# power_sheet.net
KiCad netlist of a schematic drawn in Altium Designer
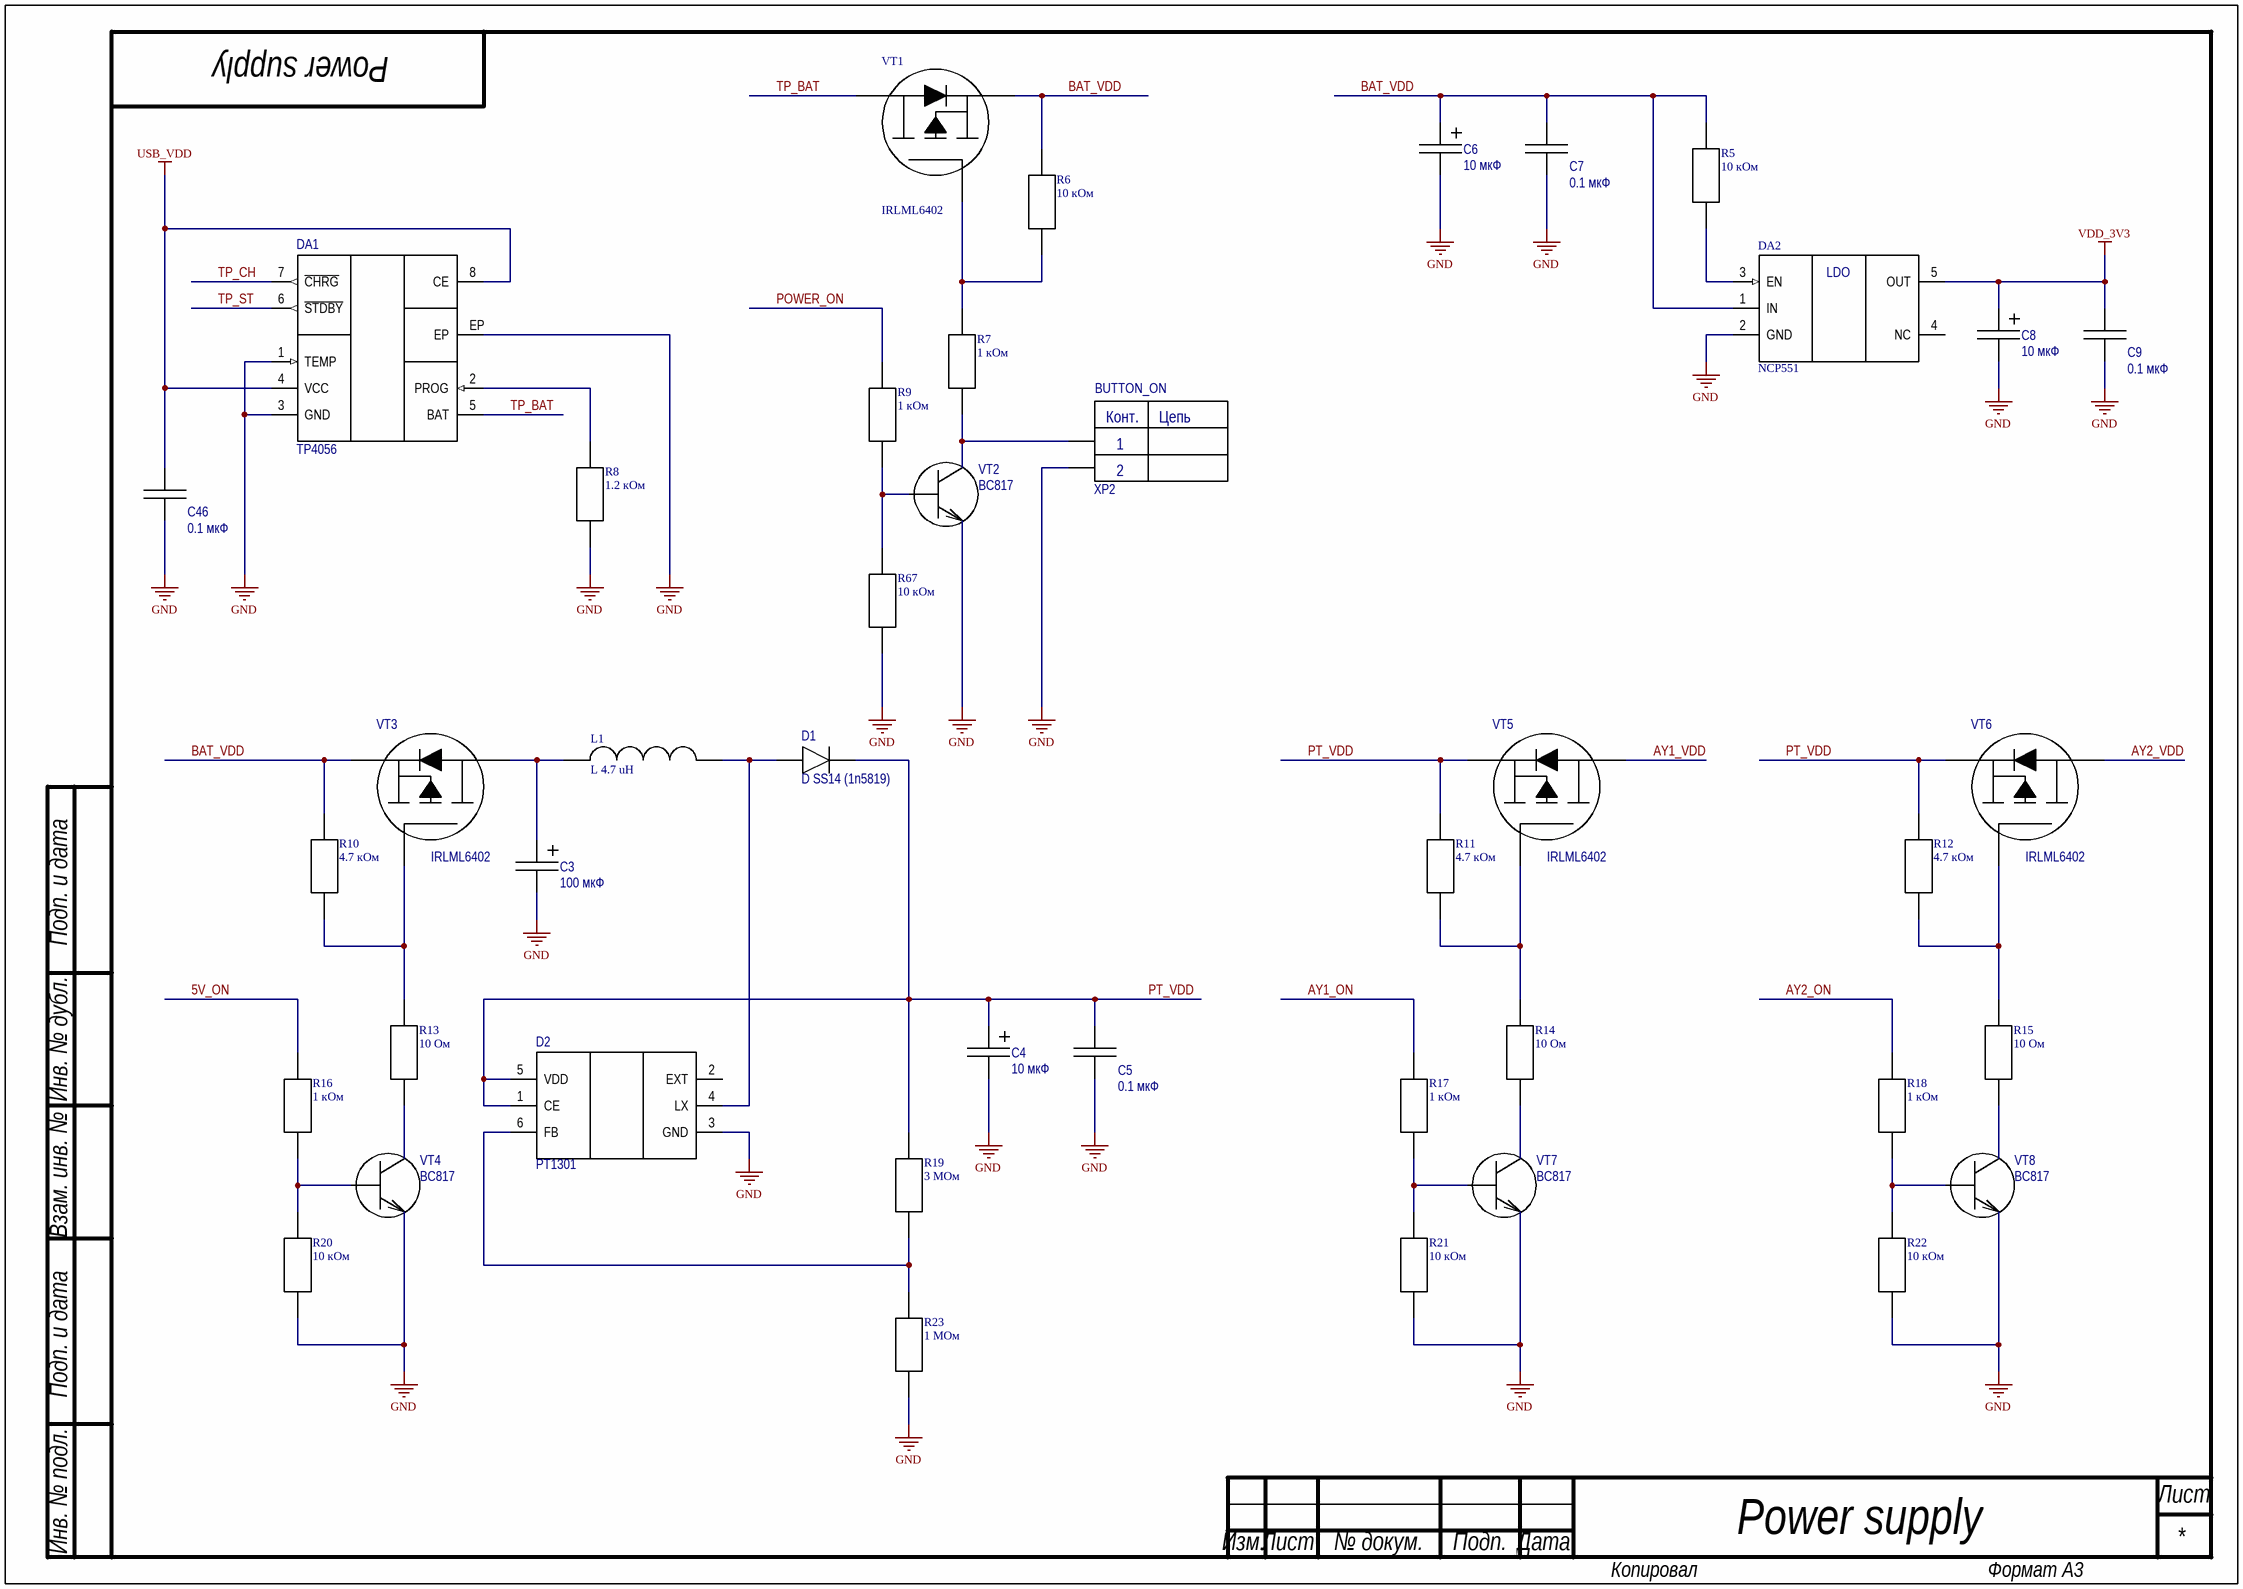
[diagram p0: power_sheet.SchDoc]

(export (version "E")
  (design (tool "Eeschema 10.0.6"))
  (components
    (comp (ref "C3")
      (value "100 мкФ")
      (footprint "C TAN_D")
      (description "SMD Tantalium Capacitor D")
      (fields
        (field (name "TOLERANCE") "/Укажите допуск в процентах/")
        (field (name "MANUFACTURER") "/Укажите компанию-производителя/")
      )
      (libsource (lib "my_lib") (part "CAP TAN_D"))
    )
    (comp (ref "C4")
      (value "10 мкФ")
      (footprint "C TAN_C")
      (description "SMD Tantalium Capacitor C")
      (fields
        (field (name "TOLERANCE") "/Укажите допуск в процентах/")
        (field (name "MANUFACTURER") "/Укажите компанию-производителя/")
      )
      (libsource (lib "my_lib") (part "CAP TAN_C"))
    )
    (comp (ref "C5")
      (value "0.1 мкФ")
      (footprint "C 1206")
      (description "SMD Capacitor 1206")
      (fields
        (field (name "TOLERANCE") "/Укажите допуск в процентах/")
        (field (name "MANUFACTURER") "/Укажите компанию-производителя/")
      )
      (libsource (lib "my_lib") (part "CAP 1206"))
    )
    (comp (ref "C6")
      (value "10 мкФ")
      (footprint "C TAN_C")
      (description "SMD Tantalium Capacitor C")
      (fields
        (field (name "TOLERANCE") "/Укажите допуск в процентах/")
        (field (name "MANUFACTURER") "/Укажите компанию-производителя/")
      )
      (libsource (lib "my_lib") (part "CAP TAN_C"))
    )
    (comp (ref "C7")
      (value "0.1 мкФ")
      (footprint "C 1206")
      (description "SMD Capacitor 1206")
      (fields
        (field (name "TOLERANCE") "/Укажите допуск в процентах/")
        (field (name "MANUFACTURER") "/Укажите компанию-производителя/")
      )
      (libsource (lib "my_lib") (part "CAP 1206"))
    )
    (comp (ref "C8")
      (value "10 мкФ")
      (footprint "C TAN_C")
      (description "SMD Tantalium Capacitor C")
      (fields
        (field (name "TOLERANCE") "/Укажите допуск в процентах/")
        (field (name "MANUFACTURER") "/Укажите компанию-производителя/")
      )
      (libsource (lib "my_lib") (part "CAP TAN_C"))
    )
    (comp (ref "C9")
      (value "0.1 мкФ")
      (footprint "C 1206")
      (description "SMD Capacitor 1206")
      (fields
        (field (name "TOLERANCE") "/Укажите допуск в процентах/")
        (field (name "MANUFACTURER") "/Укажите компанию-производителя/")
      )
      (libsource (lib "my_lib") (part "CAP 1206"))
    )
    (comp (ref "C46")
      (value "0.1 мкФ")
      (footprint "C 1206")
      (description "SMD Capacitor 1206")
      (fields
        (field (name "TOLERANCE") "/Укажите допуск в процентах/")
        (field (name "MANUFACTURER") "/Укажите компанию-производителя/")
      )
      (libsource (lib "my_lib") (part "CAP 1206"))
    )
    (comp (ref "D1")
      (value "D SS14 (1n5819)")
      (footprint "SMA/DO-214AC")
      (libsource (lib "my_lib") (part "D SS14 (1n5819)"))
    )
    (comp (ref "D2")
      (value "PT1301")
      (footprint "SOT-23-6")
      (description "DC-DC step-up (повышающий) PT1301 в корпусе SOT23-6.")
      (libsource (lib "my_lib") (part "PT1301"))
    )
    (comp (ref "DA1") (value "TP4056") (footprint "HSOP-8") (libsource (lib "my_lib") (part "TP4056")))
    (comp (ref "DA2") (value "NCP551") (footprint "TSOP-5") (libsource (lib "my_lib") (part "NCP551")))
    (comp (ref "L1")
      (value "L 4.7 uH")
      (footprint "CD43")
      (description "Катушка индуктивности 4.7 мкГн корпус CD43 (индуктивность 4.7 uH).")
      (libsource (lib "my_lib") (part "L 4.7 uH"))
    )
    (comp (ref "R5") (value "10 кОм") (footprint "RES 0805") (libsource (lib "my_lib") (part "RES 0805")))
    (comp (ref "R6") (value "10 кОм") (footprint "RES 0805") (libsource (lib "my_lib") (part "RES 0805")))
    (comp (ref "R7") (value "1 кОм") (footprint "RES 0805") (libsource (lib "my_lib") (part "RES 0805")))
    (comp (ref "R8") (value "1.2 кОм") (footprint "RES 0805") (libsource (lib "my_lib") (part "RES 0805")))
    (comp (ref "R9") (value "1 кОм") (footprint "RES 0805") (libsource (lib "my_lib") (part "RES 0805")))
    (comp (ref "R10") (value "4.7 кОм") (footprint "RES 0805") (libsource (lib "my_lib") (part "RES 0805")))
    (comp (ref "R11") (value "4.7 кОм") (footprint "RES 0805") (libsource (lib "my_lib") (part "RES 0805")))
    (comp (ref "R12") (value "4.7 кОм") (footprint "RES 0805") (libsource (lib "my_lib") (part "RES 0805")))
    (comp (ref "R13") (value "10 Ом") (footprint "RES 0805") (libsource (lib "my_lib") (part "RES 0805")))
    (comp (ref "R14") (value "10 Ом") (footprint "RES 0805") (libsource (lib "my_lib") (part "RES 0805")))
    (comp (ref "R15") (value "10 Ом") (footprint "RES 0805") (libsource (lib "my_lib") (part "RES 0805")))
    (comp (ref "R16") (value "1 кОм") (footprint "RES 0805") (libsource (lib "my_lib") (part "RES 0805")))
    (comp (ref "R17") (value "1 кОм") (footprint "RES 0805") (libsource (lib "my_lib") (part "RES 0805")))
    (comp (ref "R18") (value "1 кОм") (footprint "RES 0805") (libsource (lib "my_lib") (part "RES 0805")))
    (comp (ref "R19") (value "3 МОм") (footprint "RES 0805") (libsource (lib "my_lib") (part "RES 0805")))
    (comp (ref "R20") (value "10 кОм") (footprint "RES 0805") (libsource (lib "my_lib") (part "RES 0805")))
    (comp (ref "R21") (value "10 кОм") (footprint "RES 0805") (libsource (lib "my_lib") (part "RES 0805")))
    (comp (ref "R22") (value "10 кОм") (footprint "RES 0805") (libsource (lib "my_lib") (part "RES 0805")))
    (comp (ref "R23") (value "1 МОм") (footprint "RES 0805") (libsource (lib "my_lib") (part "RES 0805")))
    (comp (ref "R67") (value "10 кОм") (footprint "RES 0805") (libsource (lib "my_lib") (part "RES 0805")))
    (comp (ref "VT1") (value "IRLML6402") (footprint "SOT-23") (libsource (lib "my_lib") (part "IRLML6402")))
    (comp (ref "VT2")
      (value "BC817")
      (footprint "SOT-23")
      (description "NPN general-purpose transistor")
      (fields (field (name "MANUFACTURER") "NXP"))
      (libsource (lib "my_lib") (part "BC817"))
    )
    (comp (ref "VT3") (value "IRLML6402") (footprint "SOT-23") (libsource (lib "my_lib") (part "IRLML6402")))
    (comp (ref "VT4")
      (value "BC817")
      (footprint "SOT-23")
      (description "NPN general-purpose transistor")
      (fields (field (name "MANUFACTURER") "NXP"))
      (libsource (lib "my_lib") (part "BC817"))
    )
    (comp (ref "VT5") (value "IRLML6402") (footprint "SOT-23") (libsource (lib "my_lib") (part "IRLML6402")))
    (comp (ref "VT6") (value "IRLML6402") (footprint "SOT-23") (libsource (lib "my_lib") (part "IRLML6402")))
    (comp (ref "VT7")
      (value "BC817")
      (footprint "SOT-23")
      (description "NPN general-purpose transistor")
      (fields (field (name "MANUFACTURER") "NXP"))
      (libsource (lib "my_lib") (part "BC817"))
    )
    (comp (ref "VT8")
      (value "BC817")
      (footprint "SOT-23")
      (description "NPN general-purpose transistor")
      (fields (field (name "MANUFACTURER") "NXP"))
      (libsource (lib "my_lib") (part "BC817"))
    )
    (comp (ref "XP2")
      (value "PLS-2")
      (footprint "PLS-2")
      (description "PLS connector")
      (fields (field (name "MANUFACTURER") "NONAME"))
      (libsource (lib "my_lib") (part "PLS-2"))
    )
  )
  (nets
    (net (code "1") (name "/5V_ON") (class "Default")
      (node (ref "R16") (pin "2") (pinfunction "2_2") (pintype "passive"))
    )
    (net (code "2") (name "/AY1_ON") (class "Default")
      (node (ref "R17") (pin "2") (pinfunction "2_2") (pintype "passive"))
    )
    (net (code "3") (name "/AY1_VDD") (class "Default")
      (node (ref "VT5") (pin "3") (pinfunction "D_3") (pintype "passive"))
    )
    (net (code "4") (name "/AY2_ON") (class "Default")
      (node (ref "R18") (pin "2") (pinfunction "2_2") (pintype "passive"))
    )
    (net (code "5") (name "/AY2_VDD") (class "Default")
      (node (ref "VT6") (pin "3") (pinfunction "D_3") (pintype "passive"))
    )
    (net (code "6") (name "/BAT_VDD") (class "Default")
      (node (ref "C6") (pin "1") (pinfunction "1_1") (pintype "passive"))
      (node (ref "C7") (pin "1") (pinfunction "1_1") (pintype "passive"))
      (node (ref "DA2") (pin "1") (pinfunction "IN_1") (pintype "passive"))
      (node (ref "R10") (pin "2") (pinfunction "2_2") (pintype "passive"))
      (node (ref "R5") (pin "2") (pinfunction "2_2") (pintype "passive"))
      (node (ref "R6") (pin "2") (pinfunction "2_2") (pintype "passive"))
      (node (ref "VT1") (pin "2") (pinfunction "S_2") (pintype "passive"))
      (node (ref "VT3") (pin "2") (pinfunction "S_2") (pintype "passive"))
    )
    (net (code "7") (name "/POWER_ON") (class "Default")
      (node (ref "R9") (pin "2") (pinfunction "2_2") (pintype "passive"))
    )
    (net (code "8") (name "/PT_VDD") (class "Default")
      (node (ref "C4") (pin "1") (pinfunction "1_1") (pintype "passive"))
      (node (ref "C5") (pin "1") (pinfunction "1_1") (pintype "passive"))
      (node (ref "D1") (pin "C") (pinfunction "C_C") (pintype "passive"))
      (node (ref "D2") (pin "1") (pinfunction "CE_1") (pintype "passive"))
      (node (ref "D2") (pin "5") (pinfunction "VDD_5") (pintype "passive"))
      (node (ref "R11") (pin "2") (pinfunction "2_2") (pintype "passive"))
      (node (ref "R12") (pin "2") (pinfunction "2_2") (pintype "passive"))
      (node (ref "R19") (pin "2") (pinfunction "2_2") (pintype "passive"))
      (node (ref "VT5") (pin "2") (pinfunction "S_2") (pintype "passive"))
      (node (ref "VT6") (pin "2") (pinfunction "S_2") (pintype "passive"))
    )
    (net (code "9") (name "/TP_BAT") (class "Default")
      (node (ref "DA1") (pin "5") (pinfunction "BAT_5") (pintype "power_in"))
      (node (ref "VT1") (pin "3") (pinfunction "D_3") (pintype "passive"))
    )
    (net (code "10") (name "/TP_CH") (class "Default")
      (node (ref "DA1") (pin "7") (pinfunction "~{CHRG}_7") (pintype "output"))
    )
    (net (code "11") (name "/TP_ST") (class "Default")
      (node (ref "DA1") (pin "6") (pinfunction "~{STDBY}_6") (pintype "output"))
    )
    (net (code "12") (name "GND") (class "Default")
      (node (ref "C3") (pin "2") (pinfunction "2_2") (pintype "passive"))
      (node (ref "C4") (pin "2") (pinfunction "2_2") (pintype "passive"))
      (node (ref "C46") (pin "2") (pinfunction "2_2") (pintype "passive"))
      (node (ref "C5") (pin "2") (pinfunction "2_2") (pintype "passive"))
      (node (ref "C6") (pin "2") (pinfunction "2_2") (pintype "passive"))
      (node (ref "C7") (pin "2") (pinfunction "2_2") (pintype "passive"))
      (node (ref "C8") (pin "2") (pinfunction "2_2") (pintype "passive"))
      (node (ref "C9") (pin "2") (pinfunction "2_2") (pintype "passive"))
      (node (ref "D2") (pin "3") (pinfunction "GND_3") (pintype "passive"))
      (node (ref "DA1") (pin "1") (pinfunction "TEMP_1") (pintype "input"))
      (node (ref "DA1") (pin "3") (pinfunction "GND_3") (pintype "power_in"))
      (node (ref "DA1") (pin "EP") (pinfunction "EP_EP") (pintype "passive"))
      (node (ref "DA2") (pin "2") (pinfunction "GND_2") (pintype "passive"))
      (node (ref "R20") (pin "1") (pinfunction "1_1") (pintype "passive"))
      (node (ref "R21") (pin "1") (pinfunction "1_1") (pintype "passive"))
      (node (ref "R22") (pin "1") (pinfunction "1_1") (pintype "passive"))
      (node (ref "R23") (pin "1") (pinfunction "1_1") (pintype "passive"))
      (node (ref "R67") (pin "1") (pinfunction "1_1") (pintype "passive"))
      (node (ref "R8") (pin "1") (pinfunction "1_1") (pintype "passive"))
      (node (ref "VT2") (pin "2") (pinfunction "E_2") (pintype "passive"))
      (node (ref "VT4") (pin "2") (pinfunction "E_2") (pintype "passive"))
      (node (ref "VT7") (pin "2") (pinfunction "E_2") (pintype "passive"))
      (node (ref "VT8") (pin "2") (pinfunction "E_2") (pintype "passive"))
      (node (ref "XP2") (pin "2") (pinfunction "2_2") (pintype "passive"))
    )
    (net (code "13") (name "Net-(D2-FB)") (class "Default")
      (node (ref "D2") (pin "6") (pinfunction "FB_6") (pintype "passive"))
      (node (ref "R19") (pin "1") (pinfunction "1_1") (pintype "passive"))
      (node (ref "R23") (pin "2") (pinfunction "2_2") (pintype "passive"))
    )
    (net (code "14") (name "Net-(D2-LX)") (class "Default")
      (node (ref "D1") (pin "A") (pinfunction "A_A") (pintype "passive"))
      (node (ref "D2") (pin "4") (pinfunction "LX_4") (pintype "passive"))
      (node (ref "L1") (pin "2") (pinfunction "2_2") (pintype "passive"))
    )
    (net (code "15") (name "Net-(DA1-PROG)") (class "Default")
      (node (ref "DA1") (pin "2") (pinfunction "PROG_2") (pintype "input"))
      (node (ref "R8") (pin "2") (pinfunction "2_2") (pintype "passive"))
    )
    (net (code "16") (name "Net-(DA2-EN)") (class "Default")
      (node (ref "DA2") (pin "3") (pinfunction "EN_3") (pintype "input"))
      (node (ref "R5") (pin "1") (pinfunction "1_1") (pintype "passive"))
    )
    (net (code "17") (name "Net-(VT1-G)") (class "Default")
      (node (ref "R6") (pin "1") (pinfunction "1_1") (pintype "passive"))
      (node (ref "R7") (pin "2") (pinfunction "2_2") (pintype "passive"))
      (node (ref "VT1") (pin "1") (pinfunction "G_1") (pintype "passive"))
    )
    (net (code "18") (name "Net-(VT2-B)") (class "Default")
      (node (ref "R67") (pin "2") (pinfunction "2_2") (pintype "passive"))
      (node (ref "R9") (pin "1") (pinfunction "1_1") (pintype "passive"))
      (node (ref "VT2") (pin "1") (pinfunction "B_1") (pintype "passive"))
    )
    (net (code "19") (name "Net-(VT2-C)") (class "Default")
      (node (ref "R7") (pin "1") (pinfunction "1_1") (pintype "passive"))
      (node (ref "VT2") (pin "3") (pinfunction "C_3") (pintype "passive"))
      (node (ref "XP2") (pin "1") (pinfunction "1_1") (pintype "passive"))
    )
    (net (code "20") (name "Net-(VT3-D)") (class "Default")
      (node (ref "C3") (pin "1") (pinfunction "1_1") (pintype "passive"))
      (node (ref "L1") (pin "1") (pinfunction "1_1") (pintype "passive"))
      (node (ref "VT3") (pin "3") (pinfunction "D_3") (pintype "passive"))
    )
    (net (code "21") (name "Net-(VT3-G)") (class "Default")
      (node (ref "R10") (pin "1") (pinfunction "1_1") (pintype "passive"))
      (node (ref "R13") (pin "2") (pinfunction "2_2") (pintype "passive"))
      (node (ref "VT3") (pin "1") (pinfunction "G_1") (pintype "passive"))
    )
    (net (code "22") (name "Net-(VT4-B)") (class "Default")
      (node (ref "R16") (pin "1") (pinfunction "1_1") (pintype "passive"))
      (node (ref "R20") (pin "2") (pinfunction "2_2") (pintype "passive"))
      (node (ref "VT4") (pin "1") (pinfunction "B_1") (pintype "passive"))
    )
    (net (code "23") (name "Net-(VT4-C)") (class "Default")
      (node (ref "R13") (pin "1") (pinfunction "1_1") (pintype "passive"))
      (node (ref "VT4") (pin "3") (pinfunction "C_3") (pintype "passive"))
    )
    (net (code "24") (name "Net-(VT5-G)") (class "Default")
      (node (ref "R11") (pin "1") (pinfunction "1_1") (pintype "passive"))
      (node (ref "R14") (pin "2") (pinfunction "2_2") (pintype "passive"))
      (node (ref "VT5") (pin "1") (pinfunction "G_1") (pintype "passive"))
    )
    (net (code "25") (name "Net-(VT6-G)") (class "Default")
      (node (ref "R12") (pin "1") (pinfunction "1_1") (pintype "passive"))
      (node (ref "R15") (pin "2") (pinfunction "2_2") (pintype "passive"))
      (node (ref "VT6") (pin "1") (pinfunction "G_1") (pintype "passive"))
    )
    (net (code "26") (name "Net-(VT7-B)") (class "Default")
      (node (ref "R17") (pin "1") (pinfunction "1_1") (pintype "passive"))
      (node (ref "R21") (pin "2") (pinfunction "2_2") (pintype "passive"))
      (node (ref "VT7") (pin "1") (pinfunction "B_1") (pintype "passive"))
    )
    (net (code "27") (name "Net-(VT7-C)") (class "Default")
      (node (ref "R14") (pin "1") (pinfunction "1_1") (pintype "passive"))
      (node (ref "VT7") (pin "3") (pinfunction "C_3") (pintype "passive"))
    )
    (net (code "28") (name "Net-(VT8-B)") (class "Default")
      (node (ref "R18") (pin "1") (pinfunction "1_1") (pintype "passive"))
      (node (ref "R22") (pin "2") (pinfunction "2_2") (pintype "passive"))
      (node (ref "VT8") (pin "1") (pinfunction "B_1") (pintype "passive"))
    )
    (net (code "29") (name "Net-(VT8-C)") (class "Default")
      (node (ref "R15") (pin "1") (pinfunction "1_1") (pintype "passive"))
      (node (ref "VT8") (pin "3") (pinfunction "C_3") (pintype "passive"))
    )
    (net (code "30") (name "USB_VDD") (class "Default")
      (node (ref "C46") (pin "1") (pinfunction "1_1") (pintype "passive"))
      (node (ref "DA1") (pin "4") (pinfunction "VCC_4") (pintype "power_in"))
      (node (ref "DA1") (pin "8") (pinfunction "CE_8") (pintype "passive"))
    )
    (net (code "31") (name "VDD_3V3") (class "Default")
      (node (ref "C8") (pin "1") (pinfunction "1_1") (pintype "passive"))
      (node (ref "C9") (pin "1") (pinfunction "1_1") (pintype "passive"))
      (node (ref "DA2") (pin "5") (pinfunction "OUT_5") (pintype "passive"))
    )
    (net (code "32") (name "unconnected-(D2-EXT-Pad2)") (class "Default")
      (node (ref "D2") (pin "2") (pinfunction "EXT_2") (pintype "passive"))
    )
    (net (code "33") (name "unconnected-(DA2-NC-Pad4)") (class "Default")
      (node (ref "DA2") (pin "4") (pinfunction "NC_4") (pintype "passive"))
    )
  )
)
